# TS3USB3031_2-ch_2p3t_Multiplexer.net
KiCad netlist of a schematic drawn in Altium Designer
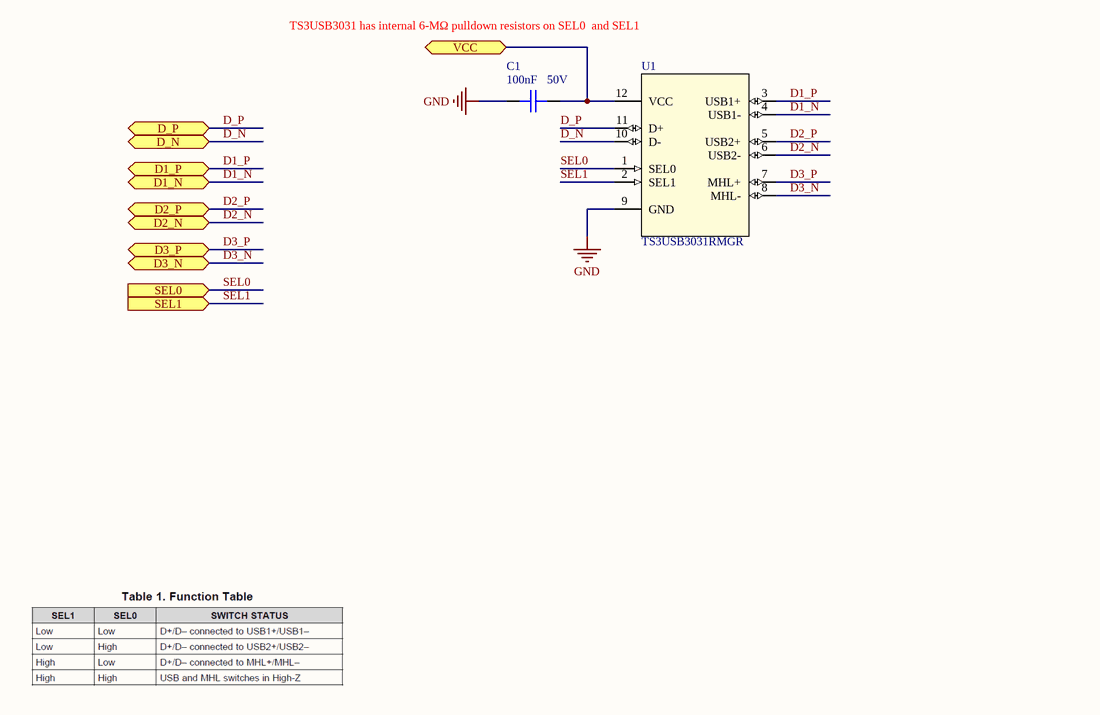
[diagram p0: TS3USB3031_2-ch_2p3t_Multiplexer.SchDoc]

(export (version "E")
  (design (tool "Eeschema 10.0.6"))
  (components
    (comp (ref "C1")
      (value "CAP CER 0.1UF 50V X7R 0402")
      (footprint "C0402")
      (description "0.1µF ±10% 50V Ceramic Capacitor X7R 0402 (1005 Metric)")
      (fields
        (field (name "MANUFACTURER") "TDK")
        (field (name "MANUFACTURER PART NUMBER") "CGA2B3X7R1H104K050BB")
        (field (name "CAPACITANCE") "100nF")
        (field (name "VOLTAGE") "50V")
      )
      (libsource (lib "capacitors_smd") (part "CAP CER 0.1UF 50V X7R 0402"))
    )
    (comp (ref "U1")
      (value "TS3USB3031RMGR")
      (footprint "RMG12_TEX")
      (description "USB Switch IC 1 Channel 12-WQFN (1.8x1.8)")
      (fields (field (name "MANUFACTURER") "Texas Instruments"))
      (libsource (lib "BLDC_Motor_Driver") (part "IC TS3USB3031 USB SWITCH DUAL 1X2 12WQFN"))
    )
  )
  (nets
    (net (code "1") (name "/D1_N") (class "Default")
      (node (ref "U1") (pin "4") (pinfunction "USB1-_4") (pintype "bidirectional"))
    )
    (net (code "2") (name "/D1_P") (class "Default")
      (node (ref "U1") (pin "3") (pinfunction "USB1+_3") (pintype "bidirectional"))
    )
    (net (code "3") (name "/D2_N") (class "Default")
      (node (ref "U1") (pin "6") (pinfunction "USB2-_6") (pintype "bidirectional"))
    )
    (net (code "4") (name "/D2_P") (class "Default")
      (node (ref "U1") (pin "5") (pinfunction "USB2+_5") (pintype "bidirectional"))
    )
    (net (code "5") (name "/D3_N") (class "Default")
      (node (ref "U1") (pin "8") (pinfunction "MHL-_8") (pintype "bidirectional"))
    )
    (net (code "6") (name "/D3_P") (class "Default")
      (node (ref "U1") (pin "7") (pinfunction "MHL+_7") (pintype "bidirectional"))
    )
    (net (code "7") (name "/D_N") (class "Default")
      (node (ref "U1") (pin "10") (pinfunction "D-_10") (pintype "bidirectional"))
    )
    (net (code "8") (name "/D_P") (class "Default")
      (node (ref "U1") (pin "11") (pinfunction "D+_11") (pintype "bidirectional"))
    )
    (net (code "9") (name "/SEL0") (class "Default")
      (node (ref "U1") (pin "1") (pinfunction "SEL0_1") (pintype "input"))
    )
    (net (code "10") (name "/SEL1") (class "Default")
      (node (ref "U1") (pin "2") (pinfunction "SEL1_2") (pintype "input"))
    )
    (net (code "11") (name "/VCC") (class "Default")
      (node (ref "C1") (pin "2") (pinfunction "2_2") (pintype "passive"))
      (node (ref "U1") (pin "12") (pinfunction "VCC_12") (pintype "power_in"))
    )
    (net (code "12") (name "GND") (class "Default")
      (node (ref "C1") (pin "1") (pinfunction "1_1") (pintype "passive"))
      (node (ref "U1") (pin "9") (pinfunction "GND_9") (pintype "power_in"))
    )
  )
)
